# EsquematicoAD.net
KiCad netlist of a schematic drawn in Altium Designer
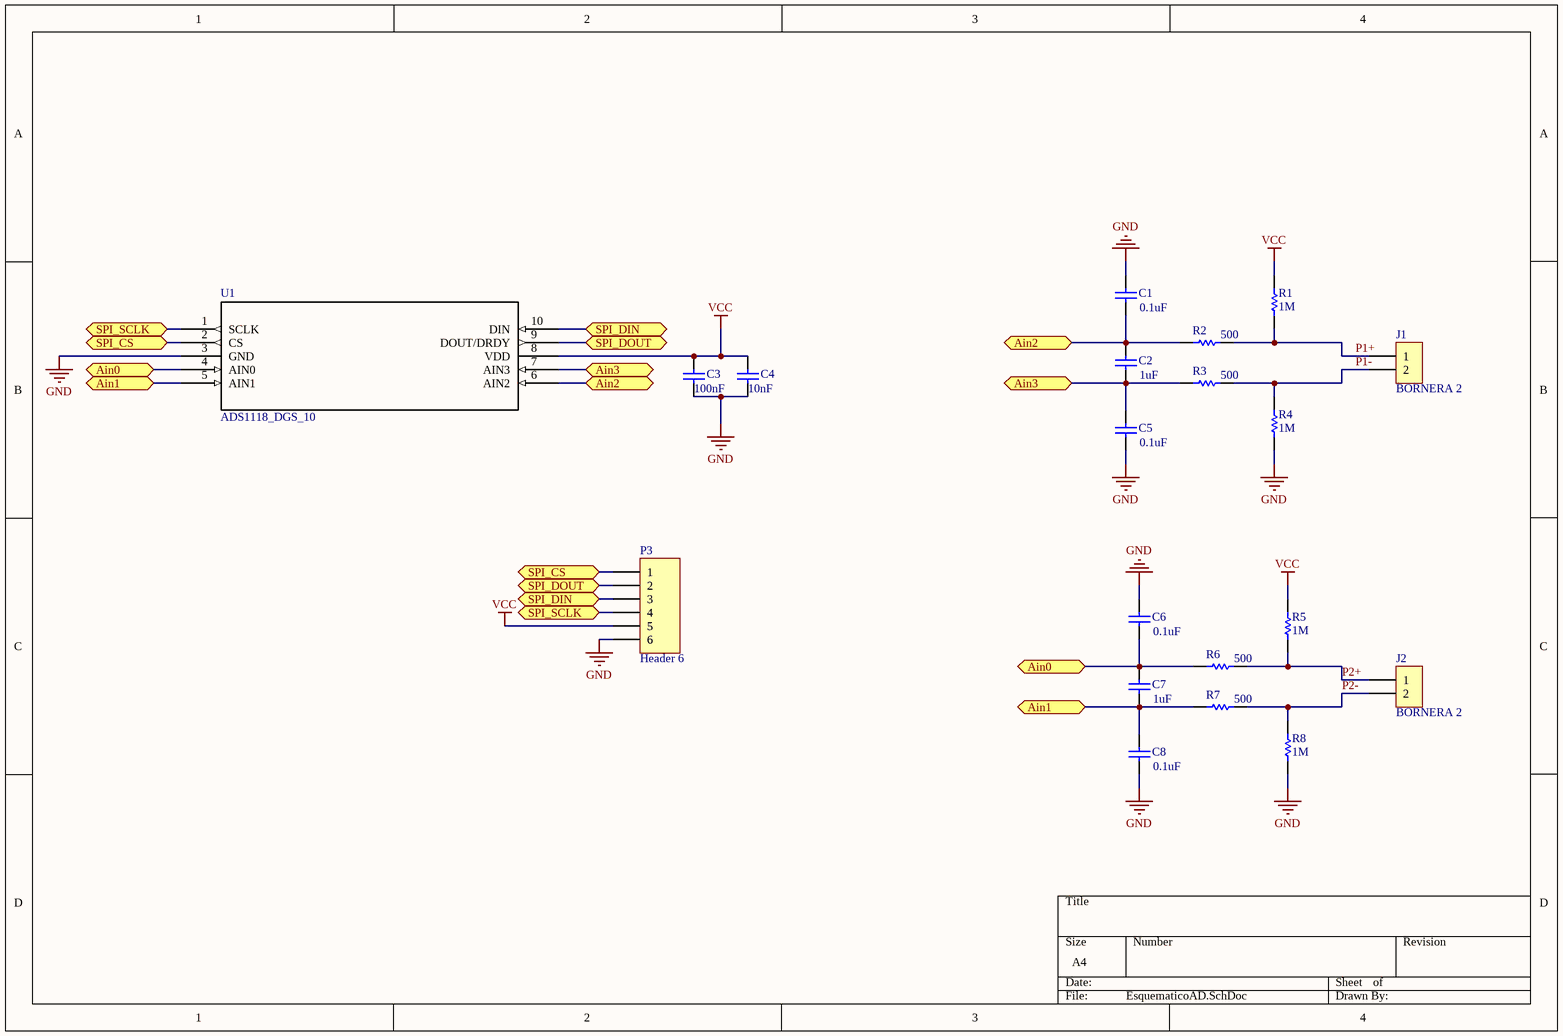
[diagram p0: EsquematicoAD.SchDoc]

(export (version "E")
  (design (tool "Eeschema 10.0.6"))
  (components
    (comp (ref "C1")
      (value "0.1uF")
      (footprint "CAPR2.54-5.1x3.2")
      (description "Capacitor")
      (fields (field (name "Comment") "Cap") (field (name "PUBLISHER") "Altium Limited"))
      (libsource (lib "Miscellaneous Devices") (part "Cap"))
    )
    (comp (ref "C2")
      (value "1uF")
      (footprint "CAPR2.54-5.1x3.2")
      (description "Capacitor")
      (fields (field (name "Comment") "Cap") (field (name "PUBLISHER") "Altium Limited"))
      (libsource (lib "Miscellaneous Devices") (part "Cap"))
    )
    (comp (ref "C3")
      (value "100nF")
      (footprint "CAPR2.54-5.1x3.2")
      (description "Capacitor")
      (fields (field (name "Comment") "Cap") (field (name "PUBLISHER") "Altium Limited"))
      (libsource (lib "Miscellaneous Devices") (part "Cap"))
    )
    (comp (ref "C4")
      (value "10nF")
      (footprint "CAPR2.54-5.1x3.2")
      (description "Capacitor")
      (fields (field (name "Comment") "Cap") (field (name "PUBLISHER") "Altium Limited"))
      (libsource (lib "Miscellaneous Devices") (part "Cap"))
    )
    (comp (ref "C5")
      (value "0.1uF")
      (footprint "CAPR2.54-5.1x3.2")
      (description "Capacitor")
      (fields (field (name "Comment") "Cap") (field (name "PUBLISHER") "Altium Limited"))
      (libsource (lib "Miscellaneous Devices") (part "Cap"))
    )
    (comp (ref "C6")
      (value "0.1uF")
      (footprint "CAPR2.54-5.1x3.2")
      (description "Capacitor")
      (fields (field (name "Comment") "Cap") (field (name "PUBLISHER") "Altium Limited"))
      (libsource (lib "Miscellaneous Devices") (part "Cap"))
    )
    (comp (ref "C7")
      (value "1uF")
      (footprint "CAPR2.54-5.1x3.2")
      (description "Capacitor")
      (fields (field (name "Comment") "Cap") (field (name "PUBLISHER") "Altium Limited"))
      (libsource (lib "Miscellaneous Devices") (part "Cap"))
    )
    (comp (ref "C8")
      (value "0.1uF")
      (footprint "CAPR2.54-5.1x3.2")
      (description "Capacitor")
      (fields (field (name "Comment") "Cap") (field (name "PUBLISHER") "Altium Limited"))
      (libsource (lib "Miscellaneous Devices") (part "Cap"))
    )
    (comp (ref "J1")
      (value "BORNERA 2")
      (footprint "BORNERA 2")
      (libsource (lib "LIBRERIA INTEGRADA MATI2") (part "BORNERA 2"))
    )
    (comp (ref "J2")
      (value "BORNERA 2")
      (footprint "BORNERA 2")
      (libsource (lib "LIBRERIA INTEGRADA MATI2") (part "BORNERA 2"))
    )
    (comp (ref "P3")
      (value "Header 6")
      (footprint "HDR1X6")
      (description "Header, 6-Pin")
      (fields (field (name "PUBLISHER") "Altium Limited"))
      (libsource (lib "Miscellaneous Connectors") (part "Header 6"))
    )
    (comp (ref "R1")
      (value "1M")
      (footprint "AXIAL-0.3")
      (description "Resistor")
      (fields (field (name "Comment") "Res1") (field (name "PUBLISHER") "Altium Limited"))
      (libsource (lib "Miscellaneous Devices") (part "Res1"))
    )
    (comp (ref "R2")
      (value "500")
      (footprint "AXIAL-0.3")
      (description "Resistor")
      (fields (field (name "Comment") "Res1") (field (name "PUBLISHER") "Altium Limited"))
      (libsource (lib "Miscellaneous Devices") (part "Res1"))
    )
    (comp (ref "R3")
      (value "500")
      (footprint "AXIAL-0.3")
      (description "Resistor")
      (fields (field (name "Comment") "Res1") (field (name "PUBLISHER") "Altium Limited"))
      (libsource (lib "Miscellaneous Devices") (part "Res1"))
    )
    (comp (ref "R4")
      (value "1M")
      (footprint "AXIAL-0.3")
      (description "Resistor")
      (fields (field (name "Comment") "Res1") (field (name "PUBLISHER") "Altium Limited"))
      (libsource (lib "Miscellaneous Devices") (part "Res1"))
    )
    (comp (ref "R5")
      (value "1M")
      (footprint "AXIAL-0.3")
      (description "Resistor")
      (fields (field (name "Comment") "Res1") (field (name "PUBLISHER") "Altium Limited"))
      (libsource (lib "Miscellaneous Devices") (part "Res1"))
    )
    (comp (ref "R6")
      (value "500")
      (footprint "AXIAL-0.3")
      (description "Resistor")
      (fields (field (name "Comment") "Res1") (field (name "PUBLISHER") "Altium Limited"))
      (libsource (lib "Miscellaneous Devices") (part "Res1"))
    )
    (comp (ref "R7")
      (value "500")
      (footprint "AXIAL-0.3")
      (description "Resistor")
      (fields (field (name "Comment") "Res1") (field (name "PUBLISHER") "Altium Limited"))
      (libsource (lib "Miscellaneous Devices") (part "Res1"))
    )
    (comp (ref "R8")
      (value "1M")
      (footprint "AXIAL-0.3")
      (description "Resistor")
      (fields (field (name "Comment") "Res1") (field (name "PUBLISHER") "Altium Limited"))
      (libsource (lib "Miscellaneous Devices") (part "Res1"))
    )
    (comp (ref "U1")
      (value "ADS1118_DGS_10")
      (footprint "DGS10")
      (description "Imported")
      (fields
        (field (name "MANUFACTURER") "Texas Instruments")
        (field (name "GENERIC_PART_NUMBER") "ADS1118")
      )
      (libsource (lib "ADS1118") (part "ADS1118_DGS_10"))
    )
  )
  (nets
    (net (code "1") (name "/Ain0") (class "Default")
      (node (ref "C6") (pin "1") (pinfunction "1_1") (pintype "passive"))
      (node (ref "C7") (pin "2") (pinfunction "2_2") (pintype "passive"))
      (node (ref "R6") (pin "1") (pinfunction "1_1") (pintype "passive"))
      (node (ref "U1") (pin "4") (pinfunction "AIN0_4") (pintype "input"))
    )
    (net (code "2") (name "/Ain1") (class "Default")
      (node (ref "C7") (pin "1") (pinfunction "1_1") (pintype "passive"))
      (node (ref "C8") (pin "2") (pinfunction "2_2") (pintype "passive"))
      (node (ref "R7") (pin "1") (pinfunction "1_1") (pintype "passive"))
      (node (ref "U1") (pin "5") (pinfunction "AIN1_5") (pintype "input"))
    )
    (net (code "3") (name "/Ain2") (class "Default")
      (node (ref "C1") (pin "1") (pinfunction "1_1") (pintype "passive"))
      (node (ref "C2") (pin "2") (pinfunction "2_2") (pintype "passive"))
      (node (ref "R2") (pin "1") (pinfunction "1_1") (pintype "passive"))
      (node (ref "U1") (pin "6") (pinfunction "AIN2_6") (pintype "input"))
    )
    (net (code "4") (name "/Ain3") (class "Default")
      (node (ref "C2") (pin "1") (pinfunction "1_1") (pintype "passive"))
      (node (ref "C5") (pin "2") (pinfunction "2_2") (pintype "passive"))
      (node (ref "R3") (pin "1") (pinfunction "1_1") (pintype "passive"))
      (node (ref "U1") (pin "7") (pinfunction "AIN3_7") (pintype "input"))
    )
    (net (code "5") (name "/P1+") (class "Default")
      (node (ref "J1") (pin "1") (pinfunction "1_1") (pintype "passive"))
      (node (ref "R1") (pin "1") (pinfunction "1_1") (pintype "passive"))
      (node (ref "R2") (pin "2") (pinfunction "2_2") (pintype "passive"))
    )
    (net (code "6") (name "/P1-") (class "Default")
      (node (ref "J1") (pin "2") (pinfunction "2_2") (pintype "passive"))
      (node (ref "R3") (pin "2") (pinfunction "2_2") (pintype "passive"))
      (node (ref "R4") (pin "1") (pinfunction "1_1") (pintype "passive"))
    )
    (net (code "7") (name "/P2+") (class "Default")
      (node (ref "J2") (pin "1") (pinfunction "1_1") (pintype "passive"))
      (node (ref "R5") (pin "1") (pinfunction "1_1") (pintype "passive"))
      (node (ref "R6") (pin "2") (pinfunction "2_2") (pintype "passive"))
    )
    (net (code "8") (name "/P2-") (class "Default")
      (node (ref "J2") (pin "2") (pinfunction "2_2") (pintype "passive"))
      (node (ref "R7") (pin "2") (pinfunction "2_2") (pintype "passive"))
      (node (ref "R8") (pin "1") (pinfunction "1_1") (pintype "passive"))
    )
    (net (code "9") (name "/SPI_CS") (class "Default")
      (node (ref "P3") (pin "1") (pinfunction "1_1") (pintype "passive"))
      (node (ref "U1") (pin "2") (pinfunction "CS_2") (pintype "output"))
    )
    (net (code "10") (name "/SPI_DIN") (class "Default")
      (node (ref "P3") (pin "3") (pinfunction "3_3") (pintype "passive"))
      (node (ref "U1") (pin "10") (pinfunction "DIN_10") (pintype "input"))
    )
    (net (code "11") (name "/SPI_DOUT") (class "Default")
      (node (ref "P3") (pin "2") (pinfunction "2_2") (pintype "passive"))
      (node (ref "U1") (pin "9") (pinfunction "DOUT/DRDY_9") (pintype "output"))
    )
    (net (code "12") (name "/SPI_SCLK") (class "Default")
      (node (ref "P3") (pin "4") (pinfunction "4_4") (pintype "passive"))
      (node (ref "U1") (pin "1") (pinfunction "SCLK_1") (pintype "output"))
    )
    (net (code "13") (name "GND") (class "Default")
      (node (ref "C1") (pin "2") (pinfunction "2_2") (pintype "passive"))
      (node (ref "C3") (pin "1") (pinfunction "1_1") (pintype "passive"))
      (node (ref "C4") (pin "1") (pinfunction "1_1") (pintype "passive"))
      (node (ref "C5") (pin "1") (pinfunction "1_1") (pintype "passive"))
      (node (ref "C6") (pin "2") (pinfunction "2_2") (pintype "passive"))
      (node (ref "C8") (pin "1") (pinfunction "1_1") (pintype "passive"))
      (node (ref "P3") (pin "6") (pinfunction "6_6") (pintype "passive"))
      (node (ref "R4") (pin "2") (pinfunction "2_2") (pintype "passive"))
      (node (ref "R8") (pin "2") (pinfunction "2_2") (pintype "passive"))
      (node (ref "U1") (pin "3") (pinfunction "GND_3") (pintype "power_in"))
    )
    (net (code "14") (name "VCC") (class "Default")
      (node (ref "C3") (pin "2") (pinfunction "2_2") (pintype "passive"))
      (node (ref "C4") (pin "2") (pinfunction "2_2") (pintype "passive"))
      (node (ref "P3") (pin "5") (pinfunction "5_5") (pintype "passive"))
      (node (ref "R1") (pin "2") (pinfunction "2_2") (pintype "passive"))
      (node (ref "R5") (pin "2") (pinfunction "2_2") (pintype "passive"))
      (node (ref "U1") (pin "8") (pinfunction "VDD_8") (pintype "power_in"))
    )
  )
)
